# 00_PINOUT.net
KiCad netlist of a schematic drawn in Altium Designer
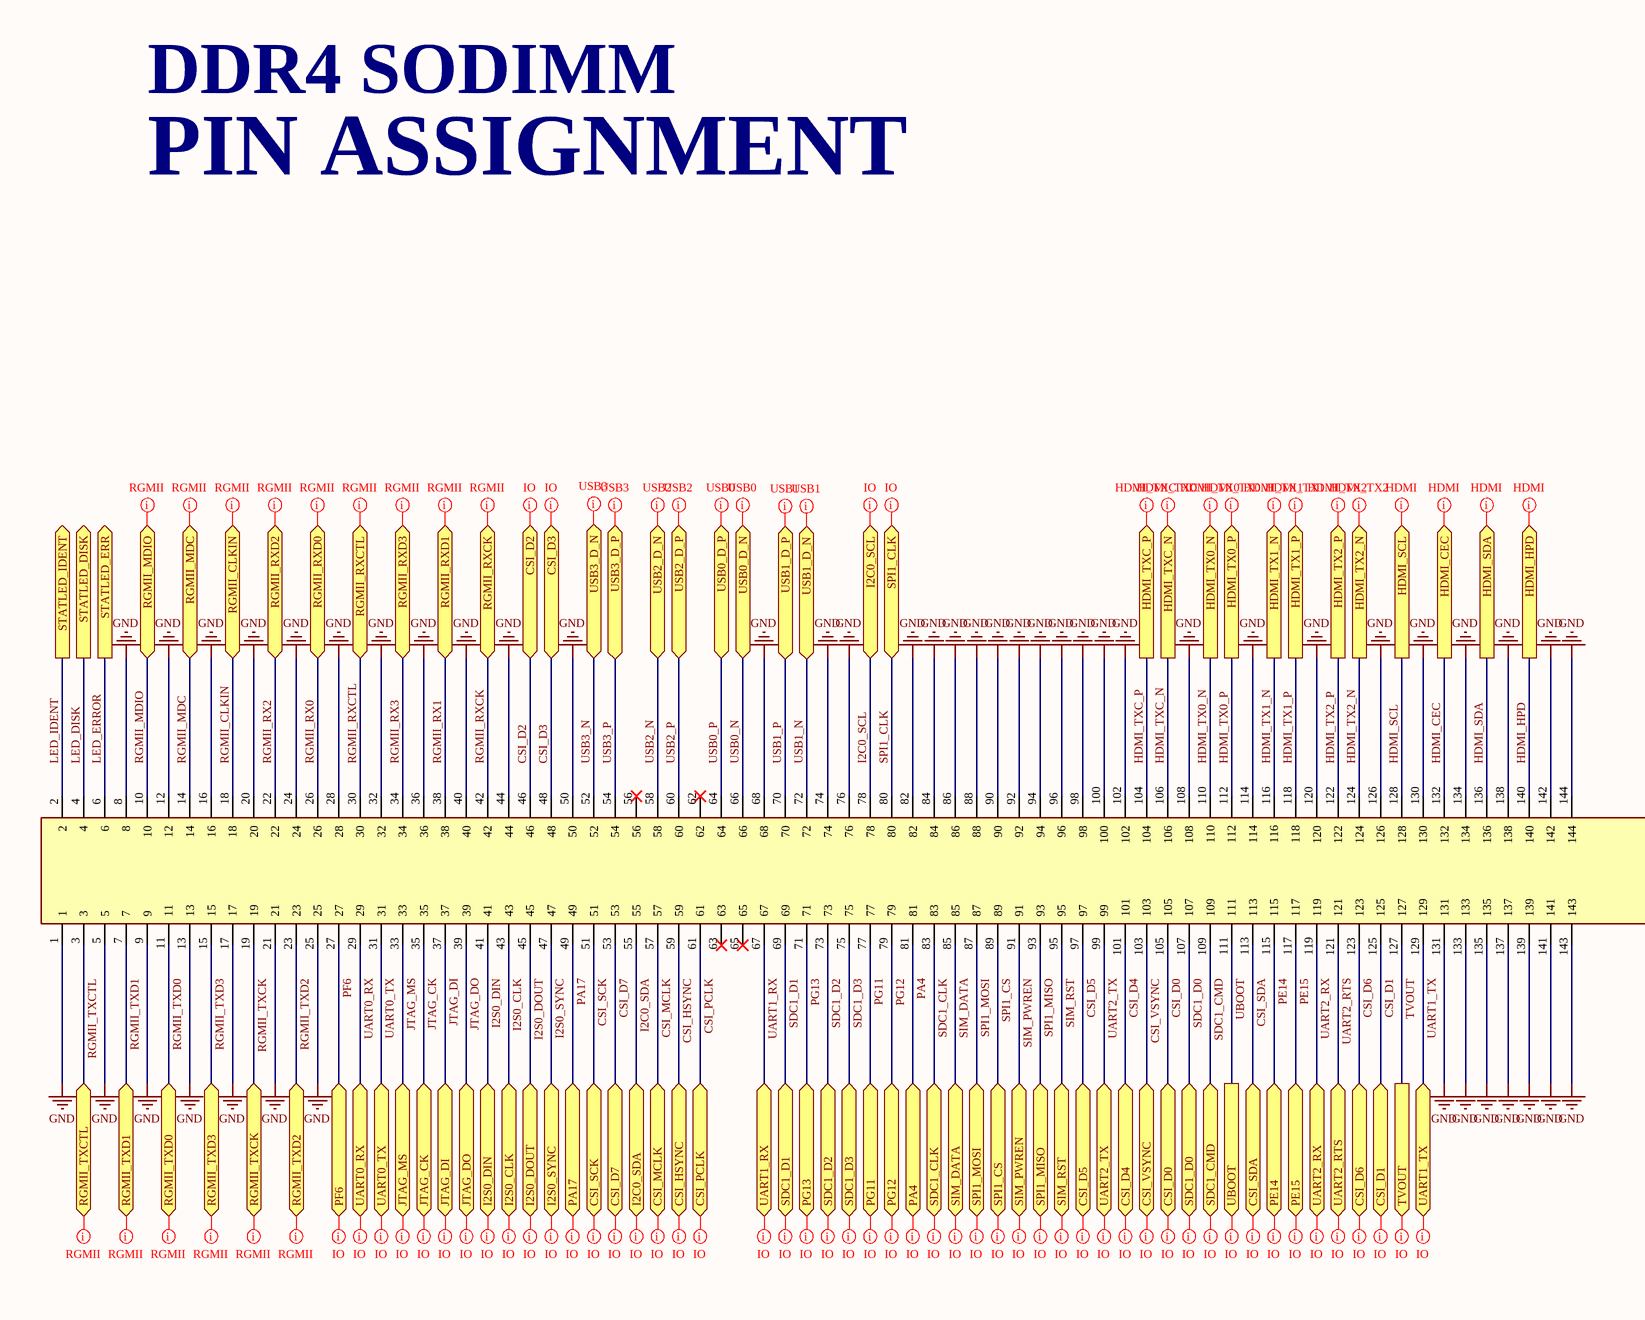
[diagram p0: 00_PINOUT.SchDoc, left]
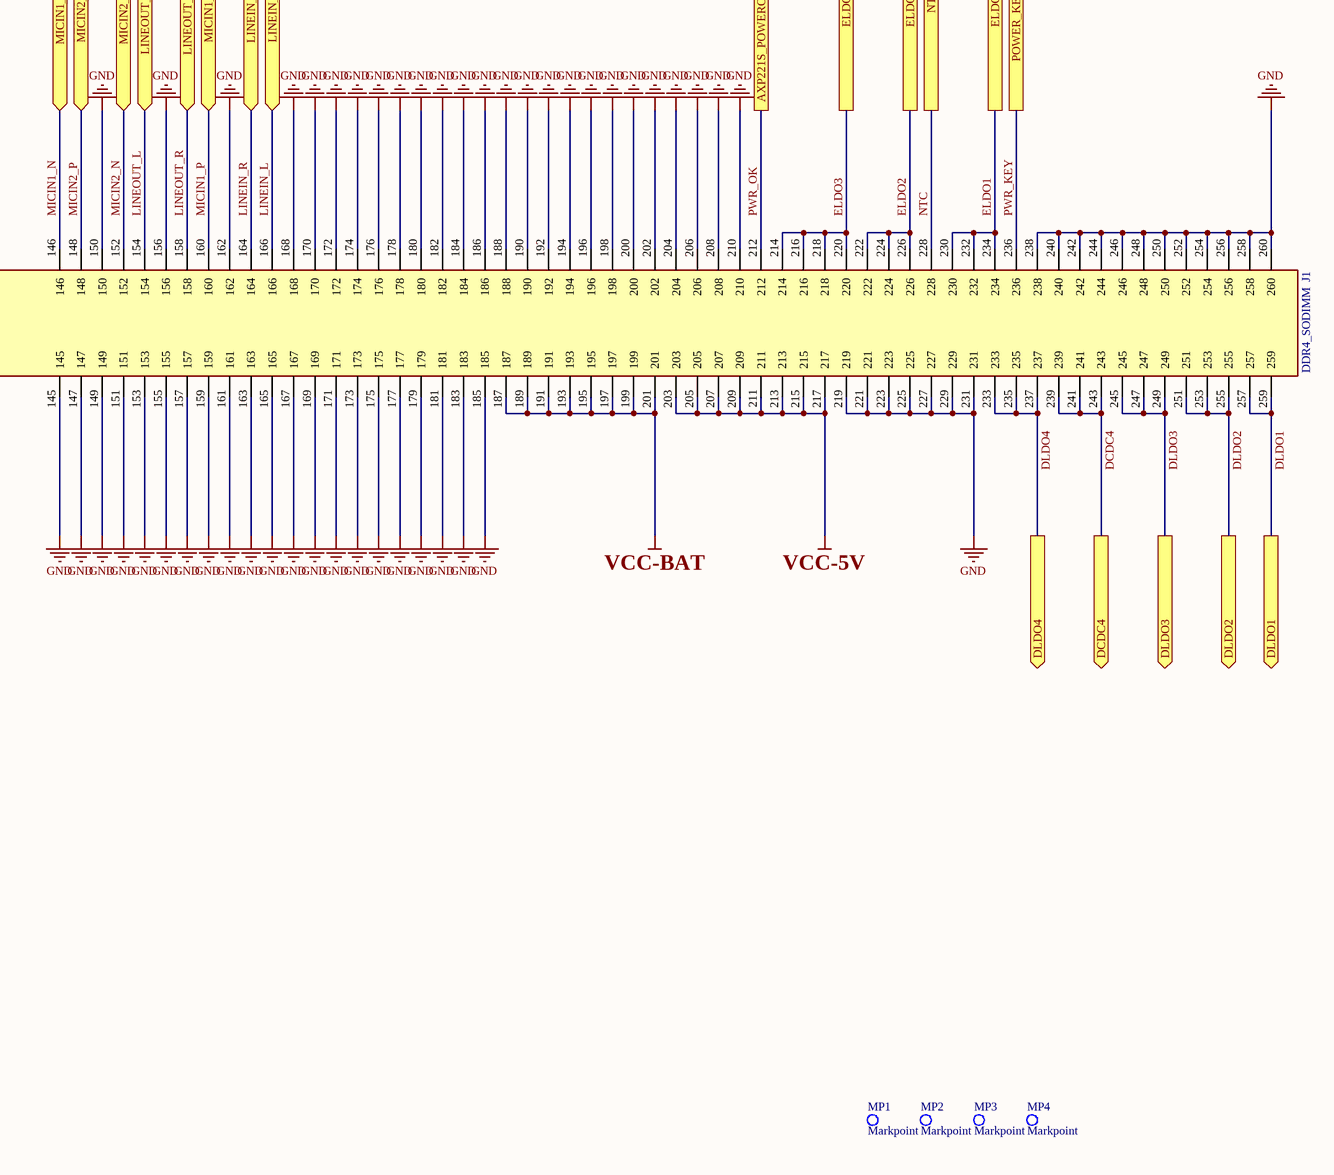
[diagram p1: 00_PINOUT.SchDoc, right]

(export (version "E")
  (design (tool "Eeschema 10.0.6"))
  (components
    (comp (ref "J1")
      (value "DDR4_SODIMM")
      (footprint "DDR4_SODIMM")
      (libsource (lib "Board") (part "DDR4_SODIMM"))
    )
    (comp (ref "MP1")
      (value "Markpoint")
      (footprint "MARKPOINT")
      (libsource (lib "Board") (part "MARKPOINT"))
    )
    (comp (ref "MP2")
      (value "Markpoint")
      (footprint "MARKPOINT")
      (libsource (lib "Board") (part "MARKPOINT"))
    )
    (comp (ref "MP3")
      (value "Markpoint")
      (footprint "MARKPOINT")
      (libsource (lib "Board") (part "MARKPOINT"))
    )
    (comp (ref "MP4")
      (value "Markpoint")
      (footprint "MARKPOINT")
      (libsource (lib "Board") (part "MARKPOINT"))
    )
  )
  (nets
    (net (code "1") (name "/CSI_D0") (class "Default")
      (node (ref "J1") (pin "105") (pinfunction "105_105") (pintype "passive"))
    )
    (net (code "2") (name "/CSI_D1") (class "Default")
      (node (ref "J1") (pin "125") (pinfunction "125_125") (pintype "passive"))
    )
    (net (code "3") (name "/CSI_D2") (class "Default")
      (node (ref "J1") (pin "46") (pinfunction "46_46") (pintype "passive"))
    )
    (net (code "4") (name "/CSI_D3") (class "Default")
      (node (ref "J1") (pin "48") (pinfunction "48_48") (pintype "passive"))
    )
    (net (code "5") (name "/CSI_D4") (class "Default")
      (node (ref "J1") (pin "101") (pinfunction "101_101") (pintype "passive"))
    )
    (net (code "6") (name "/CSI_D5") (class "Default")
      (node (ref "J1") (pin "97") (pinfunction "97_97") (pintype "passive"))
    )
    (net (code "7") (name "/CSI_D6") (class "Default")
      (node (ref "J1") (pin "123") (pinfunction "123_123") (pintype "passive"))
    )
    (net (code "8") (name "/CSI_D7") (class "Default")
      (node (ref "J1") (pin "53") (pinfunction "53_53") (pintype "passive"))
    )
    (net (code "9") (name "/CSI_HSYNC") (class "Default")
      (node (ref "J1") (pin "59") (pinfunction "59_59") (pintype "passive"))
    )
    (net (code "10") (name "/CSI_MCLK") (class "Default")
      (node (ref "J1") (pin "57") (pinfunction "57_57") (pintype "passive"))
    )
    (net (code "11") (name "/CSI_PCLK") (class "Default")
      (node (ref "J1") (pin "61") (pinfunction "61_61") (pintype "passive"))
    )
    (net (code "12") (name "/CSI_SCK") (class "Default")
      (node (ref "J1") (pin "51") (pinfunction "51_51") (pintype "passive"))
    )
    (net (code "13") (name "/CSI_SDA") (class "Default")
      (node (ref "J1") (pin "113") (pinfunction "113_113") (pintype "passive"))
    )
    (net (code "14") (name "/CSI_VSYNC") (class "Default")
      (node (ref "J1") (pin "103") (pinfunction "103_103") (pintype "passive"))
    )
    (net (code "15") (name "/DCDC4") (class "Default")
      (node (ref "J1") (pin "239") (pinfunction "239_239") (pintype "passive"))
      (node (ref "J1") (pin "241") (pinfunction "241_241") (pintype "passive"))
      (node (ref "J1") (pin "243") (pinfunction "243_243") (pintype "passive"))
    )
    (net (code "16") (name "/DLDO1") (class "Default")
      (node (ref "J1") (pin "257") (pinfunction "257_257") (pintype "passive"))
      (node (ref "J1") (pin "259") (pinfunction "259_259") (pintype "passive"))
    )
    (net (code "17") (name "/DLDO2") (class "Default")
      (node (ref "J1") (pin "251") (pinfunction "251_251") (pintype "passive"))
      (node (ref "J1") (pin "253") (pinfunction "253_253") (pintype "passive"))
      (node (ref "J1") (pin "255") (pinfunction "255_255") (pintype "passive"))
    )
    (net (code "18") (name "/DLDO3") (class "Default")
      (node (ref "J1") (pin "245") (pinfunction "245_245") (pintype "passive"))
      (node (ref "J1") (pin "247") (pinfunction "247_247") (pintype "passive"))
      (node (ref "J1") (pin "249") (pinfunction "249_249") (pintype "passive"))
    )
    (net (code "19") (name "/DLDO4") (class "Default")
      (node (ref "J1") (pin "233") (pinfunction "233_233") (pintype "passive"))
      (node (ref "J1") (pin "235") (pinfunction "235_235") (pintype "passive"))
      (node (ref "J1") (pin "237") (pinfunction "237_237") (pintype "passive"))
    )
    (net (code "20") (name "/ELDO1") (class "Default")
      (node (ref "J1") (pin "230") (pinfunction "230_230") (pintype "passive"))
      (node (ref "J1") (pin "232") (pinfunction "232_232") (pintype "passive"))
      (node (ref "J1") (pin "234") (pinfunction "234_234") (pintype "passive"))
    )
    (net (code "21") (name "/ELDO2") (class "Default")
      (node (ref "J1") (pin "222") (pinfunction "222_222") (pintype "passive"))
      (node (ref "J1") (pin "224") (pinfunction "224_224") (pintype "passive"))
      (node (ref "J1") (pin "226") (pinfunction "226_226") (pintype "passive"))
    )
    (net (code "22") (name "/ELDO3") (class "Default")
      (node (ref "J1") (pin "214") (pinfunction "214_214") (pintype "passive"))
      (node (ref "J1") (pin "216") (pinfunction "216_216") (pintype "passive"))
      (node (ref "J1") (pin "218") (pinfunction "218_218") (pintype "passive"))
      (node (ref "J1") (pin "220") (pinfunction "220_220") (pintype "passive"))
    )
    (net (code "23") (name "/HDMI_CEC") (class "Default")
      (node (ref "J1") (pin "132") (pinfunction "132_132") (pintype "passive"))
    )
    (net (code "24") (name "/HDMI_HPD") (class "Default")
      (node (ref "J1") (pin "140") (pinfunction "140_140") (pintype "passive"))
    )
    (net (code "25") (name "/HDMI_SCL") (class "Default")
      (node (ref "J1") (pin "128") (pinfunction "128_128") (pintype "passive"))
    )
    (net (code "26") (name "/HDMI_SDA") (class "Default")
      (node (ref "J1") (pin "136") (pinfunction "136_136") (pintype "passive"))
    )
    (net (code "27") (name "/HDMI_TX0_N") (class "Default")
      (node (ref "J1") (pin "110") (pinfunction "110_110") (pintype "passive"))
    )
    (net (code "28") (name "/HDMI_TX0_P") (class "Default")
      (node (ref "J1") (pin "112") (pinfunction "112_112") (pintype "passive"))
    )
    (net (code "29") (name "/HDMI_TX1_N") (class "Default")
      (node (ref "J1") (pin "116") (pinfunction "116_116") (pintype "passive"))
    )
    (net (code "30") (name "/HDMI_TX1_P") (class "Default")
      (node (ref "J1") (pin "118") (pinfunction "118_118") (pintype "passive"))
    )
    (net (code "31") (name "/HDMI_TX2_N") (class "Default")
      (node (ref "J1") (pin "124") (pinfunction "124_124") (pintype "passive"))
    )
    (net (code "32") (name "/HDMI_TX2_P") (class "Default")
      (node (ref "J1") (pin "122") (pinfunction "122_122") (pintype "passive"))
    )
    (net (code "33") (name "/HDMI_TXC_N") (class "Default")
      (node (ref "J1") (pin "106") (pinfunction "106_106") (pintype "passive"))
    )
    (net (code "34") (name "/HDMI_TXC_P") (class "Default")
      (node (ref "J1") (pin "104") (pinfunction "104_104") (pintype "passive"))
    )
    (net (code "35") (name "/I2C0_SCL") (class "Default")
      (node (ref "J1") (pin "78") (pinfunction "78_78") (pintype "passive"))
    )
    (net (code "36") (name "/I2C0_SDA") (class "Default")
      (node (ref "J1") (pin "55") (pinfunction "55_55") (pintype "passive"))
    )
    (net (code "37") (name "/I2S0_CLK") (class "Default")
      (node (ref "J1") (pin "43") (pinfunction "43_43") (pintype "passive"))
    )
    (net (code "38") (name "/I2S0_DIN") (class "Default")
      (node (ref "J1") (pin "41") (pinfunction "41_41") (pintype "passive"))
    )
    (net (code "39") (name "/I2S0_DOUT") (class "Default")
      (node (ref "J1") (pin "45") (pinfunction "45_45") (pintype "passive"))
    )
    (net (code "40") (name "/I2S0_SYNC") (class "Default")
      (node (ref "J1") (pin "47") (pinfunction "47_47") (pintype "passive"))
    )
    (net (code "41") (name "/JTAG_CK") (class "Default")
      (node (ref "J1") (pin "35") (pinfunction "35_35") (pintype "passive"))
    )
    (net (code "42") (name "/JTAG_DI") (class "Default")
      (node (ref "J1") (pin "37") (pinfunction "37_37") (pintype "passive"))
    )
    (net (code "43") (name "/JTAG_DO") (class "Default")
      (node (ref "J1") (pin "39") (pinfunction "39_39") (pintype "passive"))
    )
    (net (code "44") (name "/JTAG_MS") (class "Default")
      (node (ref "J1") (pin "33") (pinfunction "33_33") (pintype "passive"))
    )
    (net (code "45") (name "/LED_DISK") (class "Default")
      (node (ref "J1") (pin "4") (pinfunction "4_4") (pintype "passive"))
    )
    (net (code "46") (name "/LED_ERROR") (class "Default")
      (node (ref "J1") (pin "6") (pinfunction "6_6") (pintype "passive"))
    )
    (net (code "47") (name "/LED_IDENT") (class "Default")
      (node (ref "J1") (pin "2") (pinfunction "2_2") (pintype "passive"))
    )
    (net (code "48") (name "/LINEIN_L") (class "Default")
      (node (ref "J1") (pin "166") (pinfunction "166_166") (pintype "passive"))
    )
    (net (code "49") (name "/LINEIN_R") (class "Default")
      (node (ref "J1") (pin "164") (pinfunction "164_164") (pintype "passive"))
    )
    (net (code "50") (name "/LINEOUT_L") (class "Default")
      (node (ref "J1") (pin "154") (pinfunction "154_154") (pintype "passive"))
    )
    (net (code "51") (name "/LINEOUT_R") (class "Default")
      (node (ref "J1") (pin "158") (pinfunction "158_158") (pintype "passive"))
    )
    (net (code "52") (name "/MICIN1_N") (class "Default")
      (node (ref "J1") (pin "146") (pinfunction "146_146") (pintype "passive"))
    )
    (net (code "53") (name "/MICIN1_P") (class "Default")
      (node (ref "J1") (pin "160") (pinfunction "160_160") (pintype "passive"))
    )
    (net (code "54") (name "/MICIN2_N") (class "Default")
      (node (ref "J1") (pin "152") (pinfunction "152_152") (pintype "passive"))
    )
    (net (code "55") (name "/MICIN2_P") (class "Default")
      (node (ref "J1") (pin "148") (pinfunction "148_148") (pintype "passive"))
    )
    (net (code "56") (name "/NTC") (class "Default")
      (node (ref "J1") (pin "228") (pinfunction "228_228") (pintype "passive"))
    )
    (net (code "57") (name "/PA4") (class "Default")
      (node (ref "J1") (pin "81") (pinfunction "81_81") (pintype "passive"))
    )
    (net (code "58") (name "/PA17") (class "Default")
      (node (ref "J1") (pin "49") (pinfunction "49_49") (pintype "passive"))
    )
    (net (code "59") (name "/PE14") (class "Default")
      (node (ref "J1") (pin "115") (pinfunction "115_115") (pintype "passive"))
    )
    (net (code "60") (name "/PE15") (class "Default")
      (node (ref "J1") (pin "117") (pinfunction "117_117") (pintype "passive"))
    )
    (net (code "61") (name "/PF6") (class "Default")
      (node (ref "J1") (pin "27") (pinfunction "27_27") (pintype "passive"))
    )
    (net (code "62") (name "/PG11") (class "Default")
      (node (ref "J1") (pin "77") (pinfunction "77_77") (pintype "passive"))
    )
    (net (code "63") (name "/PG12") (class "Default")
      (node (ref "J1") (pin "79") (pinfunction "79_79") (pintype "passive"))
    )
    (net (code "64") (name "/PG13") (class "Default")
      (node (ref "J1") (pin "71") (pinfunction "71_71") (pintype "passive"))
    )
    (net (code "65") (name "/PWR_KEY") (class "Default")
      (node (ref "J1") (pin "236") (pinfunction "236_236") (pintype "passive"))
    )
    (net (code "66") (name "/PWR_OK") (class "Default")
      (node (ref "J1") (pin "212") (pinfunction "212_212") (pintype "passive"))
    )
    (net (code "67") (name "/RGMII_CLKIN") (class "Default")
      (node (ref "J1") (pin "18") (pinfunction "18_18") (pintype "passive"))
    )
    (net (code "68") (name "/RGMII_MDC") (class "Default")
      (node (ref "J1") (pin "14") (pinfunction "14_14") (pintype "passive"))
    )
    (net (code "69") (name "/RGMII_MDIO") (class "Default")
      (node (ref "J1") (pin "10") (pinfunction "10_10") (pintype "passive"))
    )
    (net (code "70") (name "/RGMII_RX0") (class "Default")
      (node (ref "J1") (pin "26") (pinfunction "26_26") (pintype "passive"))
    )
    (net (code "71") (name "/RGMII_RX1") (class "Default")
      (node (ref "J1") (pin "38") (pinfunction "38_38") (pintype "passive"))
    )
    (net (code "72") (name "/RGMII_RX2") (class "Default")
      (node (ref "J1") (pin "22") (pinfunction "22_22") (pintype "passive"))
    )
    (net (code "73") (name "/RGMII_RX3") (class "Default")
      (node (ref "J1") (pin "34") (pinfunction "34_34") (pintype "passive"))
    )
    (net (code "74") (name "/RGMII_RXCK") (class "Default")
      (node (ref "J1") (pin "42") (pinfunction "42_42") (pintype "passive"))
    )
    (net (code "75") (name "/RGMII_RXCTL") (class "Default")
      (node (ref "J1") (pin "30") (pinfunction "30_30") (pintype "passive"))
    )
    (net (code "76") (name "/RGMII_TXCK") (class "Default")
      (node (ref "J1") (pin "19") (pinfunction "19_19") (pintype "passive"))
    )
    (net (code "77") (name "/RGMII_TXCTL") (class "Default")
      (node (ref "J1") (pin "3") (pinfunction "3_3") (pintype "passive"))
    )
    (net (code "78") (name "/RGMII_TXD0") (class "Default")
      (node (ref "J1") (pin "11") (pinfunction "11_11") (pintype "passive"))
    )
    (net (code "79") (name "/RGMII_TXD1") (class "Default")
      (node (ref "J1") (pin "7") (pinfunction "7_7") (pintype "passive"))
    )
    (net (code "80") (name "/RGMII_TXD2") (class "Default")
      (node (ref "J1") (pin "23") (pinfunction "23_23") (pintype "passive"))
    )
    (net (code "81") (name "/RGMII_TXD3") (class "Default")
      (node (ref "J1") (pin "15") (pinfunction "15_15") (pintype "passive"))
    )
    (net (code "82") (name "/SDC1_CLK") (class "Default")
      (node (ref "J1") (pin "83") (pinfunction "83_83") (pintype "passive"))
    )
    (net (code "83") (name "/SDC1_CMD") (class "Default")
      (node (ref "J1") (pin "109") (pinfunction "109_109") (pintype "passive"))
    )
    (net (code "84") (name "/SDC1_D0") (class "Default")
      (node (ref "J1") (pin "107") (pinfunction "107_107") (pintype "passive"))
    )
    (net (code "85") (name "/SDC1_D1") (class "Default")
      (node (ref "J1") (pin "69") (pinfunction "69_69") (pintype "passive"))
    )
    (net (code "86") (name "/SDC1_D2") (class "Default")
      (node (ref "J1") (pin "73") (pinfunction "73_73") (pintype "passive"))
    )
    (net (code "87") (name "/SDC1_D3") (class "Default")
      (node (ref "J1") (pin "75") (pinfunction "75_75") (pintype "passive"))
    )
    (net (code "88") (name "/SIM_DATA") (class "Default")
      (node (ref "J1") (pin "85") (pinfunction "85_85") (pintype "passive"))
    )
    (net (code "89") (name "/SIM_PWREN") (class "Default")
      (node (ref "J1") (pin "91") (pinfunction "91_91") (pintype "passive"))
    )
    (net (code "90") (name "/SIM_RST") (class "Default")
      (node (ref "J1") (pin "95") (pinfunction "95_95") (pintype "passive"))
    )
    (net (code "91") (name "/SPI1_CLK") (class "Default")
      (node (ref "J1") (pin "80") (pinfunction "80_80") (pintype "passive"))
    )
    (net (code "92") (name "/SPI1_CS") (class "Default")
      (node (ref "J1") (pin "89") (pinfunction "89_89") (pintype "passive"))
    )
    (net (code "93") (name "/SPI1_MISO") (class "Default")
      (node (ref "J1") (pin "93") (pinfunction "93_93") (pintype "passive"))
    )
    (net (code "94") (name "/SPI1_MOSI") (class "Default")
      (node (ref "J1") (pin "87") (pinfunction "87_87") (pintype "passive"))
    )
    (net (code "95") (name "/TVOUT") (class "Default")
      (node (ref "J1") (pin "127") (pinfunction "127_127") (pintype "passive"))
    )
    (net (code "96") (name "/UART0_RX") (class "Default")
      (node (ref "J1") (pin "29") (pinfunction "29_29") (pintype "passive"))
    )
    (net (code "97") (name "/UART0_TX") (class "Default")
      (node (ref "J1") (pin "31") (pinfunction "31_31") (pintype "passive"))
    )
    (net (code "98") (name "/UART1_RX") (class "Default")
      (node (ref "J1") (pin "67") (pinfunction "67_67") (pintype "passive"))
    )
    (net (code "99") (name "/UART1_TX") (class "Default")
      (node (ref "J1") (pin "129") (pinfunction "129_129") (pintype "passive"))
    )
    (net (code "100") (name "/UART2_RTS") (class "Default")
      (node (ref "J1") (pin "121") (pinfunction "121_121") (pintype "passive"))
    )
    (net (code "101") (name "/UART2_RX") (class "Default")
      (node (ref "J1") (pin "119") (pinfunction "119_119") (pintype "passive"))
    )
    (net (code "102") (name "/UART2_TX") (class "Default")
      (node (ref "J1") (pin "99") (pinfunction "99_99") (pintype "passive"))
    )
    (net (code "103") (name "/UBOOT") (class "Default")
      (node (ref "J1") (pin "111") (pinfunction "111_111") (pintype "passive"))
    )
    (net (code "104") (name "/USB0_N") (class "Default")
      (node (ref "J1") (pin "66") (pinfunction "66_66") (pintype "passive"))
    )
    (net (code "105") (name "/USB0_P") (class "Default")
      (node (ref "J1") (pin "64") (pinfunction "64_64") (pintype "passive"))
    )
    (net (code "106") (name "/USB1_N") (class "Default")
      (node (ref "J1") (pin "72") (pinfunction "72_72") (pintype "passive"))
    )
    (net (code "107") (name "/USB1_P") (class "Default")
      (node (ref "J1") (pin "70") (pinfunction "70_70") (pintype "passive"))
    )
    (net (code "108") (name "/USB2_N") (class "Default")
      (node (ref "J1") (pin "58") (pinfunction "58_58") (pintype "passive"))
    )
    (net (code "109") (name "/USB2_P") (class "Default")
      (node (ref "J1") (pin "60") (pinfunction "60_60") (pintype "passive"))
    )
    (net (code "110") (name "/USB3_N") (class "Default")
      (node (ref "J1") (pin "52") (pinfunction "52_52") (pintype "passive"))
    )
    (net (code "111") (name "/USB3_P") (class "Default")
      (node (ref "J1") (pin "54") (pinfunction "54_54") (pintype "passive"))
    )
    (net (code "112") (name "GND") (class "Default")
      (node (ref "J1") (pin "1") (pinfunction "1_1") (pintype "passive"))
      (node (ref "J1") (pin "100") (pinfunction "100_100") (pintype "passive"))
      (node (ref "J1") (pin "102") (pinfunction "102_102") (pintype "passive"))
      (node (ref "J1") (pin "108") (pinfunction "108_108") (pintype "passive"))
      (node (ref "J1") (pin "114") (pinfunction "114_114") (pintype "passive"))
      (node (ref "J1") (pin "12") (pinfunction "12_12") (pintype "passive"))
      (node (ref "J1") (pin "120") (pinfunction "120_120") (pintype "passive"))
      (node (ref "J1") (pin "126") (pinfunction "126_126") (pintype "passive"))
      (node (ref "J1") (pin "13") (pinfunction "13_13") (pintype "passive"))
      (node (ref "J1") (pin "130") (pinfunction "130_130") (pintype "passive"))
      (node (ref "J1") (pin "131") (pinfunction "131_131") (pintype "passive"))
      (node (ref "J1") (pin "133") (pinfunction "133_133") (pintype "passive"))
      (node (ref "J1") (pin "134") (pinfunction "134_134") (pintype "passive"))
      (node (ref "J1") (pin "135") (pinfunction "135_135") (pintype "passive"))
      (node (ref "J1") (pin "137") (pinfunction "137_137") (pintype "passive"))
      (node (ref "J1") (pin "138") (pinfunction "138_138") (pintype "passive"))
      (node (ref "J1") (pin "139") (pinfunction "139_139") (pintype "passive"))
      (node (ref "J1") (pin "141") (pinfunction "141_141") (pintype "passive"))
      (node (ref "J1") (pin "142") (pinfunction "142_142") (pintype "passive"))
      (node (ref "J1") (pin "143") (pinfunction "143_143") (pintype "passive"))
      (node (ref "J1") (pin "144") (pinfunction "144_144") (pintype "passive"))
      (node (ref "J1") (pin "145") (pinfunction "145_145") (pintype "passive"))
      (node (ref "J1") (pin "147") (pinfunction "147_147") (pintype "passive"))
      (node (ref "J1") (pin "149") (pinfunction "149_149") (pintype "passive"))
      (node (ref "J1") (pin "150") (pinfunction "150_150") (pintype "passive"))
      (node (ref "J1") (pin "151") (pinfunction "151_151") (pintype "passive"))
      (node (ref "J1") (pin "153") (pinfunction "153_153") (pintype "passive"))
      (node (ref "J1") (pin "155") (pinfunction "155_155") (pintype "passive"))
      (node (ref "J1") (pin "156") (pinfunction "156_156") (pintype "passive"))
      (node (ref "J1") (pin "157") (pinfunction "157_157") (pintype "passive"))
      (node (ref "J1") (pin "159") (pinfunction "159_159") (pintype "passive"))
      (node (ref "J1") (pin "16") (pinfunction "16_16") (pintype "passive"))
      (node (ref "J1") (pin "161") (pinfunction "161_161") (pintype "passive"))
      (node (ref "J1") (pin "162") (pinfunction "162_162") (pintype "passive"))
      (node (ref "J1") (pin "163") (pinfunction "163_163") (pintype "passive"))
      (node (ref "J1") (pin "165") (pinfunction "165_165") (pintype "passive"))
      (node (ref "J1") (pin "167") (pinfunction "167_167") (pintype "passive"))
      (node (ref "J1") (pin "168") (pinfunction "168_168") (pintype "passive"))
      (node (ref "J1") (pin "169") (pinfunction "169_169") (pintype "passive"))
      (node (ref "J1") (pin "17") (pinfunction "17_17") (pintype "passive"))
      (node (ref "J1") (pin "170") (pinfunction "170_170") (pintype "passive"))
      (node (ref "J1") (pin "171") (pinfunction "171_171") (pintype "passive"))
      (node (ref "J1") (pin "172") (pinfunction "172_172") (pintype "passive"))
      (node (ref "J1") (pin "173") (pinfunction "173_173") (pintype "passive"))
      (node (ref "J1") (pin "174") (pinfunction "174_174") (pintype "passive"))
      (node (ref "J1") (pin "175") (pinfunction "175_175") (pintype "passive"))
      (node (ref "J1") (pin "176") (pinfunction "176_176") (pintype "passive"))
      (node (ref "J1") (pin "177") (pinfunction "177_177") (pintype "passive"))
      (node (ref "J1") (pin "178") (pinfunction "178_178") (pintype "passive"))
      (node (ref "J1") (pin "179") (pinfunction "179_179") (pintype "passive"))
      (node (ref "J1") (pin "180") (pinfunction "180_180") (pintype "passive"))
      (node (ref "J1") (pin "181") (pinfunction "181_181") (pintype "passive"))
      (node (ref "J1") (pin "182") (pinfunction "182_182") (pintype "passive"))
      (node (ref "J1") (pin "183") (pinfunction "183_183") (pintype "passive"))
      (node (ref "J1") (pin "184") (pinfunction "184_184") (pintype "passive"))
      (node (ref "J1") (pin "185") (pinfunction "185_185") (pintype "passive"))
      (node (ref "J1") (pin "186") (pinfunction "186_186") (pintype "passive"))
      (node (ref "J1") (pin "188") (pinfunction "188_188") (pintype "passive"))
      (node (ref "J1") (pin "190") (pinfunction "190_190") (pintype "passive"))
      (node (ref "J1") (pin "192") (pinfunction "192_192") (pintype "passive"))
      (node (ref "J1") (pin "194") (pinfunction "194_194") (pintype "passive"))
      (node (ref "J1") (pin "196") (pinfunction "196_196") (pintype "passive"))
      (node (ref "J1") (pin "198") (pinfunction "198_198") (pintype "passive"))
      (node (ref "J1") (pin "20") (pinfunction "20_20") (pintype "passive"))
      (node (ref "J1") (pin "200") (pinfunction "200_200") (pintype "passive"))
      (node (ref "J1") (pin "202") (pinfunction "202_202") (pintype "passive"))
      (node (ref "J1") (pin "204") (pinfunction "204_204") (pintype "passive"))
      (node (ref "J1") (pin "206") (pinfunction "206_206") (pintype "passive"))
      (node (ref "J1") (pin "208") (pinfunction "208_208") (pintype "passive"))
      (node (ref "J1") (pin "21") (pinfunction "21_21") (pintype "passive"))
      (node (ref "J1") (pin "210") (pinfunction "210_210") (pintype "passive"))
      (node (ref "J1") (pin "219") (pinfunction "219_219") (pintype "passive"))
      (node (ref "J1") (pin "221") (pinfunction "221_221") (pintype "passive"))
      (node (ref "J1") (pin "223") (pinfunction "223_223") (pintype "passive"))
      (node (ref "J1") (pin "225") (pinfunction "225_225") (pintype "passive"))
      (node (ref "J1") (pin "227") (pinfunction "227_227") (pintype "passive"))
      (node (ref "J1") (pin "229") (pinfunction "229_229") (pintype "passive"))
      (node (ref "J1") (pin "231") (pinfunction "231_231") (pintype "passive"))
      (node (ref "J1") (pin "238") (pinfunction "238_238") (pintype "passive"))
      (node (ref "J1") (pin "24") (pinfunction "24_24") (pintype "passive"))
      (node (ref "J1") (pin "240") (pinfunction "240_240") (pintype "passive"))
      (node (ref "J1") (pin "242") (pinfunction "242_242") (pintype "passive"))
      (node (ref "J1") (pin "244") (pinfunction "244_244") (pintype "passive"))
      (node (ref "J1") (pin "246") (pinfunction "246_246") (pintype "passive"))
      (node (ref "J1") (pin "248") (pinfunction "248_248") (pintype "passive"))
      (node (ref "J1") (pin "25") (pinfunction "25_25") (pintype "passive"))
      (node (ref "J1") (pin "250") (pinfunction "250_250") (pintype "passive"))
      (node (ref "J1") (pin "252") (pinfunction "252_252") (pintype "passive"))
      (node (ref "J1") (pin "254") (pinfunction "254_254") (pintype "passive"))
      (node (ref "J1") (pin "256") (pinfunction "256_256") (pintype "passive"))
      (node (ref "J1") (pin "258") (pinfunction "258_258") (pintype "passive"))
      (node (ref "J1") (pin "260") (pinfunction "260_260") (pintype "passive"))
      (node (ref "J1") (pin "28") (pinfunction "28_28") (pintype "passive"))
      (node (ref "J1") (pin "32") (pinfunction "32_32") (pintype "passive"))
      (node (ref "J1") (pin "36") (pinfunction "36_36") (pintype "passive"))
      (node (ref "J1") (pin "40") (pinfunction "40_40") (pintype "passive"))
      (node (ref "J1") (pin "44") (pinfunction "44_44") (pintype "passive"))
      (node (ref "J1") (pin "5") (pinfunction "5_5") (pintype "passive"))
      (node (ref "J1") (pin "50") (pinfunction "50_50") (pintype "passive"))
      (node (ref "J1") (pin "68") (pinfunction "68_68") (pintype "passive"))
      (node (ref "J1") (pin "74") (pinfunction "74_74") (pintype "passive"))
      (node (ref "J1") (pin "76") (pinfunction "76_76") (pintype "passive"))
      (node (ref "J1") (pin "8") (pinfunction "8_8") (pintype "passive"))
      (node (ref "J1") (pin "82") (pinfunction "82_82") (pintype "passive"))
      (node (ref "J1") (pin "84") (pinfunction "84_84") (pintype "passive"))
      (node (ref "J1") (pin "86") (pinfunction "86_86") (pintype "passive"))
      (node (ref "J1") (pin "88") (pinfunction "88_88") (pintype "passive"))
      (node (ref "J1") (pin "9") (pinfunction "9_9") (pintype "passive"))
      (node (ref "J1") (pin "90") (pinfunction "90_90") (pintype "passive"))
      (node (ref "J1") (pin "92") (pinfunction "92_92") (pintype "passive"))
      (node (ref "J1") (pin "94") (pinfunction "94_94") (pintype "passive"))
      (node (ref "J1") (pin "96") (pinfunction "96_96") (pintype "passive"))
      (node (ref "J1") (pin "98") (pinfunction "98_98") (pintype "passive"))
    )
    (net (code "113") (name "VCC-5V") (class "Default")
      (node (ref "J1") (pin "203") (pinfunction "203_203") (pintype "passive"))
      (node (ref "J1") (pin "205") (pinfunction "205_205") (pintype "passive"))
      (node (ref "J1") (pin "207") (pinfunction "207_207") (pintype "passive"))
      (node (ref "J1") (pin "209") (pinfunction "209_209") (pintype "passive"))
      (node (ref "J1") (pin "211") (pinfunction "211_211") (pintype "passive"))
      (node (ref "J1") (pin "213") (pinfunction "213_213") (pintype "passive"))
      (node (ref "J1") (pin "215") (pinfunction "215_215") (pintype "passive"))
      (node (ref "J1") (pin "217") (pinfunction "217_217") (pintype "passive"))
    )
    (net (code "114") (name "VCC-BAT") (class "Default")
      (node (ref "J1") (pin "187") (pinfunction "187_187") (pintype "passive"))
      (node (ref "J1") (pin "189") (pinfunction "189_189") (pintype "passive"))
      (node (ref "J1") (pin "191") (pinfunction "191_191") (pintype "passive"))
      (node (ref "J1") (pin "193") (pinfunction "193_193") (pintype "passive"))
      (node (ref "J1") (pin "195") (pinfunction "195_195") (pintype "passive"))
      (node (ref "J1") (pin "197") (pinfunction "197_197") (pintype "passive"))
      (node (ref "J1") (pin "199") (pinfunction "199_199") (pintype "passive"))
      (node (ref "J1") (pin "201") (pinfunction "201_201") (pintype "passive"))
    )
    (net (code "115") (name "unconnected-(J1-Pad56)") (class "Default")
      (node (ref "J1") (pin "56") (pinfunction "56_56") (pintype "passive+no_connect"))
    )
    (net (code "116") (name "unconnected-(J1-Pad62)") (class "Default")
      (node (ref "J1") (pin "62") (pinfunction "62_62") (pintype "passive+no_connect"))
    )
    (net (code "117") (name "unconnected-(J1-Pad63)") (class "Default")
      (node (ref "J1") (pin "63") (pinfunction "63_63") (pintype "passive+no_connect"))
    )
    (net (code "118") (name "unconnected-(J1-Pad65)") (class "Default")
      (node (ref "J1") (pin "65") (pinfunction "65_65") (pintype "passive+no_connect"))
    )
  )
)
